# 0121-dcdc1805030.net
KiCad netlist of a schematic drawn in EAGLE
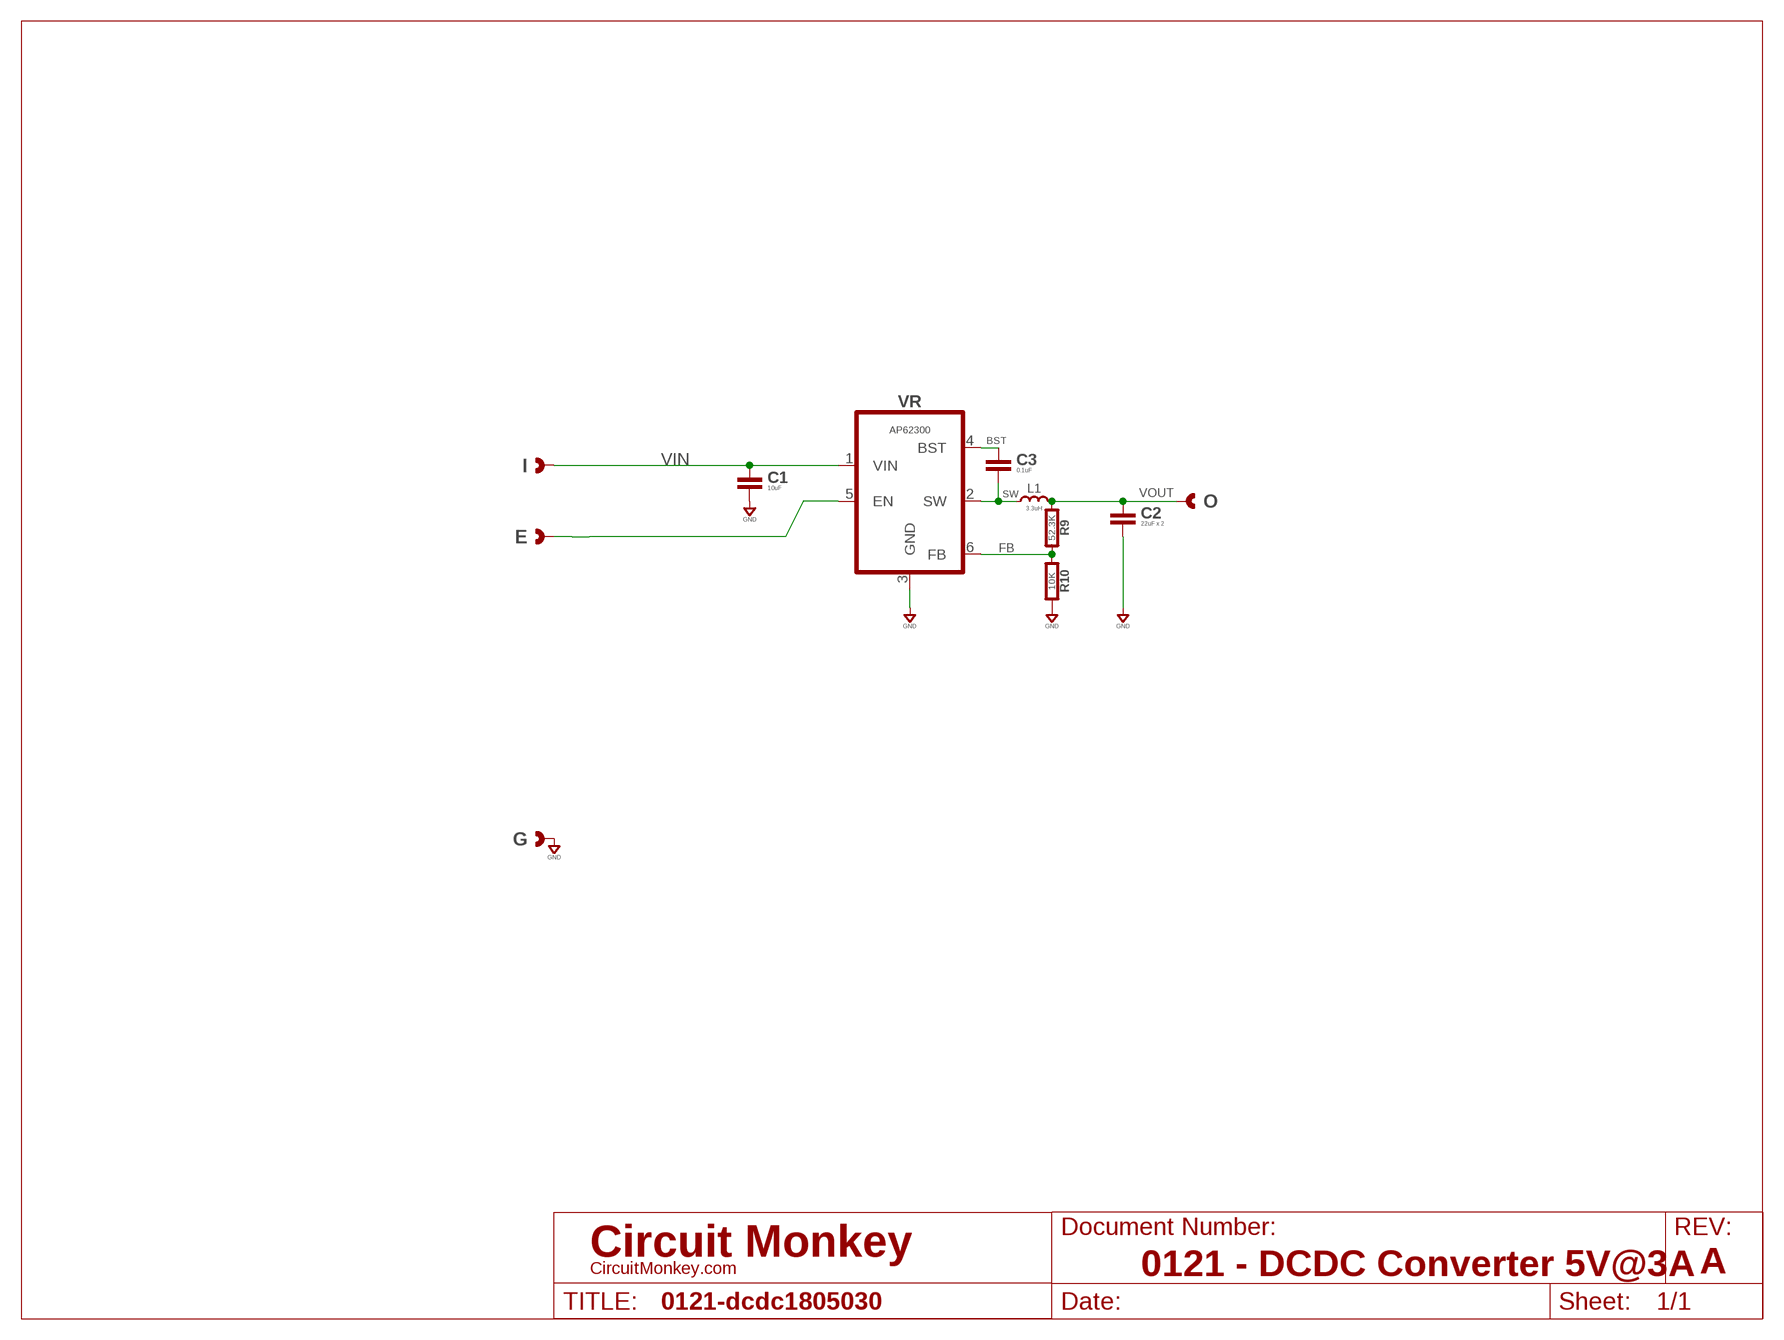
[diagram p0: schematic, sheet 1]

(export (version "E")
  (design (tool "Eeschema 10.0.6"))
  (components
    (comp (ref "C1")
      (value "10uF")
      (footprint "eagle-import:0603-CAP")
      (libsource (lib "eagle-import") (part "CAPACITOR0603"))
    )
    (comp (ref "C2")
      (value "22uF x 2")
      (footprint "eagle-import:0603-CAP")
      (libsource (lib "eagle-import") (part "CAPACITOR0603"))
    )
    (comp (ref "C3")
      (value "0.1uF")
      (footprint "eagle-import:0603-CAP")
      (libsource (lib "eagle-import") (part "CAPACITOR0603"))
    )
    (comp (ref "E")
      (value "CAST-01X12.00MM")
      (footprint "eagle-import:CAST01-2.00MM")
      (libsource (lib "eagle-import") (part "CAST-01X12.00MM"))
    )
    (comp (ref "G")
      (value "CAST-01X12.00MM")
      (footprint "eagle-import:CAST01-2.00MM")
      (libsource (lib "eagle-import") (part "CAST-01X12.00MM"))
    )
    (comp (ref "I")
      (value "CAST-01X12.00MM")
      (footprint "eagle-import:CAST01-2.00MM")
      (libsource (lib "eagle-import") (part "CAST-01X12.00MM"))
    )
    (comp (ref "L1")
      (value "3.3uH")
      (footprint "eagle-import:IND-SRN5040")
      (fields
        (field (name "MFR") "Bourns")
        (field (name "MPN") "SRN5040")
        (field (name "MPN_1") "SRN5040-3R3M")
      )
      (libsource (lib "eagle-import") (part "INDUCTORSMD-05X04MM"))
    )
    (comp (ref "O")
      (value "CAST-01X12.00MM")
      (footprint "eagle-import:CAST01-2.00MM")
      (libsource (lib "eagle-import") (part "CAST-01X12.00MM"))
    )
    (comp (ref "R9")
      (value "52.3K")
      (footprint "eagle-import:0603-RES")
      (libsource (lib "eagle-import") (part "RESISTOR0603"))
    )
    (comp (ref "R10")
      (value "10K")
      (footprint "eagle-import:0603-RES")
      (libsource (lib "eagle-import") (part "RESISTOR0603"))
    )
    (comp (ref "VR")
      (value "AP62300")
      (footprint "eagle-import:SOT-563-6")
      (fields (field (name "MFR") "Diodes, Inc.") (field (name "MPN") "AP62301Z6-7"))
      (libsource (lib "eagle-import") (part "BUCKAP62300"))
    )
  )
  (nets
    (net (code "1") (name "/BST") (class "Default")
      (node (ref "C3") (pin "1") (pinfunction "1_1") (pintype "passive"))
      (node (ref "VR") (pin "4") (pinfunction "BST_4") (pintype "bidirectional"))
    )
    (net (code "2") (name "/FB") (class "Default")
      (node (ref "R10") (pin "1") (pinfunction "1_1") (pintype "passive"))
      (node (ref "R9") (pin "2") (pinfunction "2_2") (pintype "passive"))
      (node (ref "VR") (pin "6") (pinfunction "FB_6") (pintype "bidirectional"))
    )
    (net (code "3") (name "/SW") (class "Default")
      (node (ref "C3") (pin "2") (pinfunction "2_2") (pintype "passive"))
      (node (ref "L1") (pin "2") (pinfunction "P$2_2") (pintype "passive"))
      (node (ref "VR") (pin "2") (pinfunction "SW_2") (pintype "bidirectional"))
    )
    (net (code "4") (name "/VIN") (class "Default")
      (node (ref "C1") (pin "1") (pinfunction "1_1") (pintype "passive"))
      (node (ref "I") (pin "1") (pinfunction "1_1") (pintype "bidirectional"))
      (node (ref "I") (pin "P$1") (pinfunction "1_P$1") (pintype "bidirectional"))
      (node (ref "I") (pin "P$2") (pinfunction "1_P$2") (pintype "bidirectional"))
      (node (ref "VR") (pin "1") (pinfunction "VIN_1") (pintype "bidirectional"))
    )
    (net (code "5") (name "/VOUT") (class "Default")
      (node (ref "C2") (pin "1") (pinfunction "1_1") (pintype "passive"))
      (node (ref "L1") (pin "1") (pinfunction "P$1_1") (pintype "passive"))
      (node (ref "O") (pin "1") (pinfunction "1_1") (pintype "bidirectional"))
      (node (ref "O") (pin "P$1") (pinfunction "1_P$1") (pintype "bidirectional"))
      (node (ref "O") (pin "P$2") (pinfunction "1_P$2") (pintype "bidirectional"))
      (node (ref "R9") (pin "1") (pinfunction "1_1") (pintype "passive"))
    )
    (net (code "6") (name "GND") (class "Default")
      (node (ref "C1") (pin "2") (pinfunction "2_2") (pintype "passive"))
      (node (ref "C2") (pin "2") (pinfunction "2_2") (pintype "passive"))
      (node (ref "G") (pin "1") (pinfunction "1_1") (pintype "bidirectional"))
      (node (ref "G") (pin "P$1") (pinfunction "1_P$1") (pintype "bidirectional"))
      (node (ref "G") (pin "P$2") (pinfunction "1_P$2") (pintype "bidirectional"))
      (node (ref "R10") (pin "2") (pinfunction "2_2") (pintype "passive"))
      (node (ref "VR") (pin "3") (pinfunction "GND_3") (pintype "bidirectional"))
    )
    (net (code "7") (name "Net-(VR-EN)") (class "Default")
      (node (ref "E") (pin "1") (pinfunction "1_1") (pintype "bidirectional"))
      (node (ref "E") (pin "P$1") (pinfunction "1_P$1") (pintype "bidirectional"))
      (node (ref "E") (pin "P$2") (pinfunction "1_P$2") (pintype "bidirectional"))
      (node (ref "VR") (pin "5") (pinfunction "EN_5") (pintype "bidirectional"))
    )
  )
)
